# remote_board.net
KiCad netlist of a schematic drawn in EAGLE
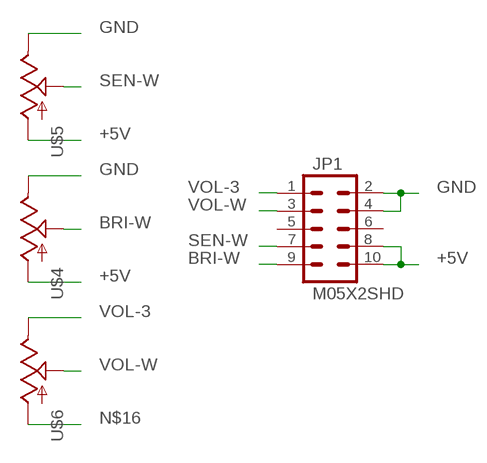
[diagram p0: schematic, sheet 1]

(export (version "E")
  (design (tool "Eeschema 10.0.6"))
  (components
    (comp (ref "JP1")
      (value "M05X2SHD")
      (footprint "eagle-import:2X5-SHROUDED")
      (libsource (lib "eagle-import") (part "M05X2SHD"))
    )
    (comp (ref "U$4")
      (value "POT100K_3362U")
      (footprint "eagle-import:3362U")
      (libsource (lib "eagle-import") (part "POT100K_3362U"))
    )
    (comp (ref "U$5")
      (value "POT100K_3362U")
      (footprint "eagle-import:3362U")
      (libsource (lib "eagle-import") (part "POT100K_3362U"))
    )
    (comp (ref "U$6")
      (value "POT100K_3362U")
      (footprint "eagle-import:3362U")
      (libsource (lib "eagle-import") (part "POT100K_3362U"))
    )
  )
  (nets
    (net (code "1") (name "/+5V") (class "Default")
      (node (ref "JP1") (pin "10") (pinfunction "10_10") (pintype "passive"))
      (node (ref "JP1") (pin "8") (pinfunction "8_8") (pintype "passive"))
      (node (ref "U$4") (pin "P$3") (pinfunction "A_P$3") (pintype "passive"))
      (node (ref "U$5") (pin "P$3") (pinfunction "A_P$3") (pintype "passive"))
    )
    (net (code "2") (name "/BRI-W") (class "Default")
      (node (ref "JP1") (pin "9") (pinfunction "9_9") (pintype "passive"))
      (node (ref "U$4") (pin "P$2") (pinfunction "S_P$2") (pintype "passive"))
    )
    (net (code "3") (name "/GND") (class "Default")
      (node (ref "JP1") (pin "2") (pinfunction "2_2") (pintype "passive"))
      (node (ref "JP1") (pin "4") (pinfunction "4_4") (pintype "passive"))
      (node (ref "U$4") (pin "P$1") (pinfunction "E_P$1") (pintype "passive"))
      (node (ref "U$5") (pin "P$1") (pinfunction "E_P$1") (pintype "passive"))
    )
    (net (code "4") (name "/N$16") (class "Default")
      (node (ref "U$6") (pin "P$3") (pinfunction "A_P$3") (pintype "passive"))
    )
    (net (code "5") (name "/SEN-W") (class "Default")
      (node (ref "JP1") (pin "7") (pinfunction "7_7") (pintype "passive"))
      (node (ref "U$5") (pin "P$2") (pinfunction "S_P$2") (pintype "passive"))
    )
    (net (code "6") (name "/VOL-3") (class "Default")
      (node (ref "JP1") (pin "1") (pinfunction "1_1") (pintype "passive"))
      (node (ref "U$6") (pin "P$1") (pinfunction "E_P$1") (pintype "passive"))
    )
    (net (code "7") (name "/VOL-W") (class "Default")
      (node (ref "JP1") (pin "3") (pinfunction "3_3") (pintype "passive"))
      (node (ref "U$6") (pin "P$2") (pinfunction "S_P$2") (pintype "passive"))
    )
    (net (code "8") (name "unconnected-(JP1-Pad5)") (class "Default")
      (node (ref "JP1") (pin "5") (pinfunction "5_5") (pintype "passive"))
    )
    (net (code "9") (name "unconnected-(JP1-Pad6)") (class "Default")
      (node (ref "JP1") (pin "6") (pinfunction "6_6") (pintype "passive"))
    )
  )
)
